# ui-pcb.net
KiCad netlist of a schematic drawn in Altium Designer
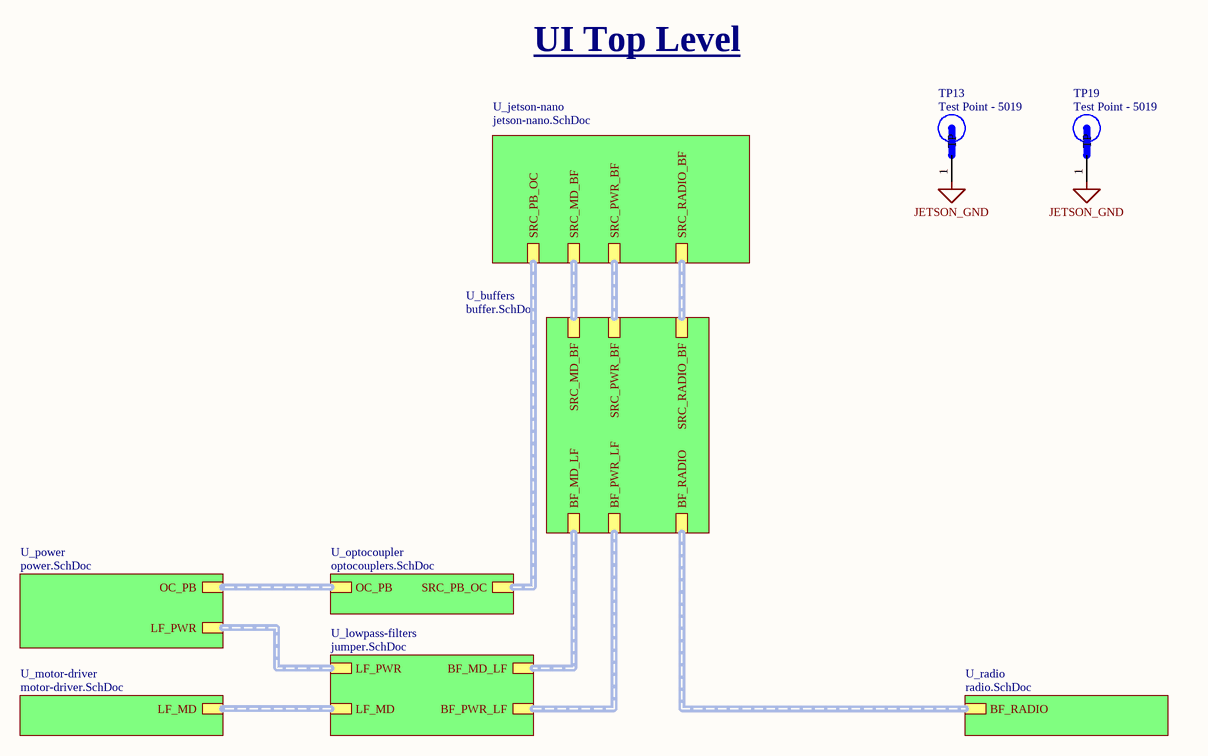
[diagram p0: ui-pcb.SchDoc]

(export (version "E")
  (design (tool "Eeschema 10.0.6"))
  (components
    (comp (ref "TP13")
      (value "Test Point - 5019")
      (footprint "TP380X203")
      (description "PC Test Point, Miniature Phosphor Bronze, Silver Plating Surface Mount Mounting Type")
      (fields (field (name "MP") "5019") (field (name "MF") "Keystone Electronics"))
      (libsource (lib "IC_Library") (part "Test Point - 5019"))
    )
    (comp (ref "TP19")
      (value "Test Point - 5019")
      (footprint "TP380X203")
      (description "PC Test Point, Miniature Phosphor Bronze, Silver Plating Surface Mount Mounting Type")
      (fields (field (name "MP") "5019") (field (name "MF") "Keystone Electronics"))
      (libsource (lib "IC_Library") (part "Test Point - 5019"))
    )
  )
  (nets
    (net (code "11") (name "JETSON_GND") (class "Default")
      (node (ref "TP13") (pin "1") (pinfunction "TP_1") (pintype "passive"))
      (node (ref "TP19") (pin "1") (pinfunction "TP_1") (pintype "passive"))
    )
  )
)
